# Window_Controller.net
KiCad netlist of a schematic drawn in EAGLE
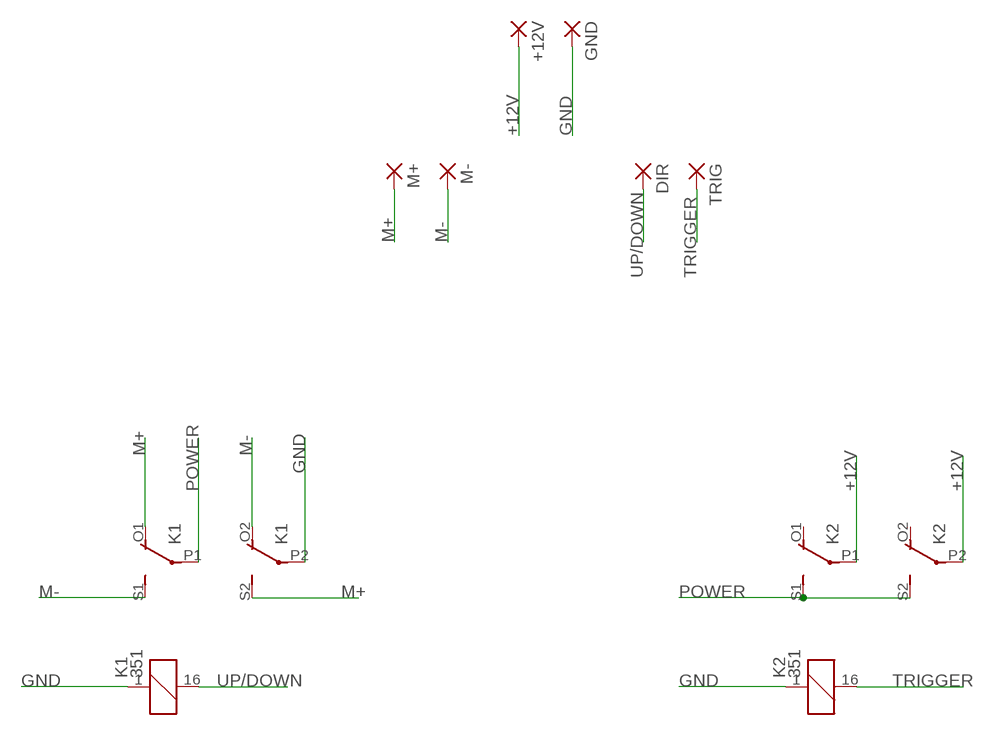
[diagram p0: schematic, sheet 1]

(export (version "E")
  (design (tool "Eeschema 10.0.6"))
  (components
    (comp (ref "+12V")
      (value "3,81/1,4")
      (footprint "eagle-import:3,81_1,4")
      (libsource (lib "eagle-import") (part "3,81/1,4"))
    )
    (comp (ref "DIR")
      (value "3,81/1,4")
      (footprint "eagle-import:3,81_1,4")
      (libsource (lib "eagle-import") (part "3,81/1,4"))
    )
    (comp (ref "GND")
      (value "3,81/1,4")
      (footprint "eagle-import:3,81_1,4")
      (libsource (lib "eagle-import") (part "3,81/1,4"))
    )
    (comp (ref "K1")
      (value "351")
      (footprint "eagle-import:351")
      (libsource (lib "eagle-import") (part "351"))
    )
    (comp (ref "K2")
      (value "351")
      (footprint "eagle-import:351")
      (libsource (lib "eagle-import") (part "351"))
    )
    (comp (ref "M+")
      (value "3,81/1,4")
      (footprint "eagle-import:3,81_1,4")
      (libsource (lib "eagle-import") (part "3,81/1,4"))
    )
    (comp (ref "M-")
      (value "3,81/1,4")
      (footprint "eagle-import:3,81_1,4")
      (libsource (lib "eagle-import") (part "3,81/1,4"))
    )
    (comp (ref "TRIG")
      (value "3,81/1,4")
      (footprint "eagle-import:3,81_1,4")
      (libsource (lib "eagle-import") (part "3,81/1,4"))
    )
  )
  (nets
    (net (code "1") (name "/+12V") (class "Default")
      (node (ref "+12V") (pin "1") (pinfunction "P_1") (pintype "passive"))
      (node (ref "K2") (pin "P1") (pinfunction "P_P1") (pintype "passive"))
      (node (ref "K2") (pin "P2") (pinfunction "P_P2") (pintype "passive"))
    )
    (net (code "2") (name "/GND") (class "Default")
      (node (ref "GND") (pin "1") (pinfunction "P_1") (pintype "passive"))
      (node (ref "K1") (pin "1") (pinfunction "1_1") (pintype "passive"))
      (node (ref "K1") (pin "P2") (pinfunction "P_P2") (pintype "passive"))
      (node (ref "K2") (pin "1") (pinfunction "1_1") (pintype "passive"))
    )
    (net (code "3") (name "/M+") (class "Default")
      (node (ref "K1") (pin "O1") (pinfunction "O_O1") (pintype "passive"))
      (node (ref "K1") (pin "S2") (pinfunction "S_S2") (pintype "passive"))
      (node (ref "M+") (pin "1") (pinfunction "P_1") (pintype "passive"))
    )
    (net (code "4") (name "/M-") (class "Default")
      (node (ref "K1") (pin "O2") (pinfunction "O_O2") (pintype "passive"))
      (node (ref "K1") (pin "S1") (pinfunction "S_S1") (pintype "passive"))
      (node (ref "M-") (pin "1") (pinfunction "P_1") (pintype "passive"))
    )
    (net (code "5") (name "/POWER") (class "Default")
      (node (ref "K1") (pin "P1") (pinfunction "P_P1") (pintype "passive"))
      (node (ref "K2") (pin "S1") (pinfunction "S_S1") (pintype "passive"))
      (node (ref "K2") (pin "S2") (pinfunction "S_S2") (pintype "passive"))
    )
    (net (code "6") (name "/TRIGGER") (class "Default")
      (node (ref "K2") (pin "16") (pinfunction "2_16") (pintype "passive"))
      (node (ref "TRIG") (pin "1") (pinfunction "P_1") (pintype "passive"))
    )
    (net (code "7") (name "/UP{slash}DOWN") (class "Default")
      (node (ref "DIR") (pin "1") (pinfunction "P_1") (pintype "passive"))
      (node (ref "K1") (pin "16") (pinfunction "2_16") (pintype "passive"))
    )
    (net (code "8") (name "unconnected-(K2B-O-PadO1)") (class "Default")
      (node (ref "K2") (pin "O1") (pinfunction "O_O1") (pintype "passive"))
    )
    (net (code "9") (name "unconnected-(K2C-O-PadO2)") (class "Default")
      (node (ref "K2") (pin "O2") (pinfunction "O_O2") (pintype "passive"))
    )
  )
)
